# 1_SWAP_21DD__LV_DR_BRUSH_REV1_0_schdoc.net
KiCad netlist of a schematic drawn in Altium Designer
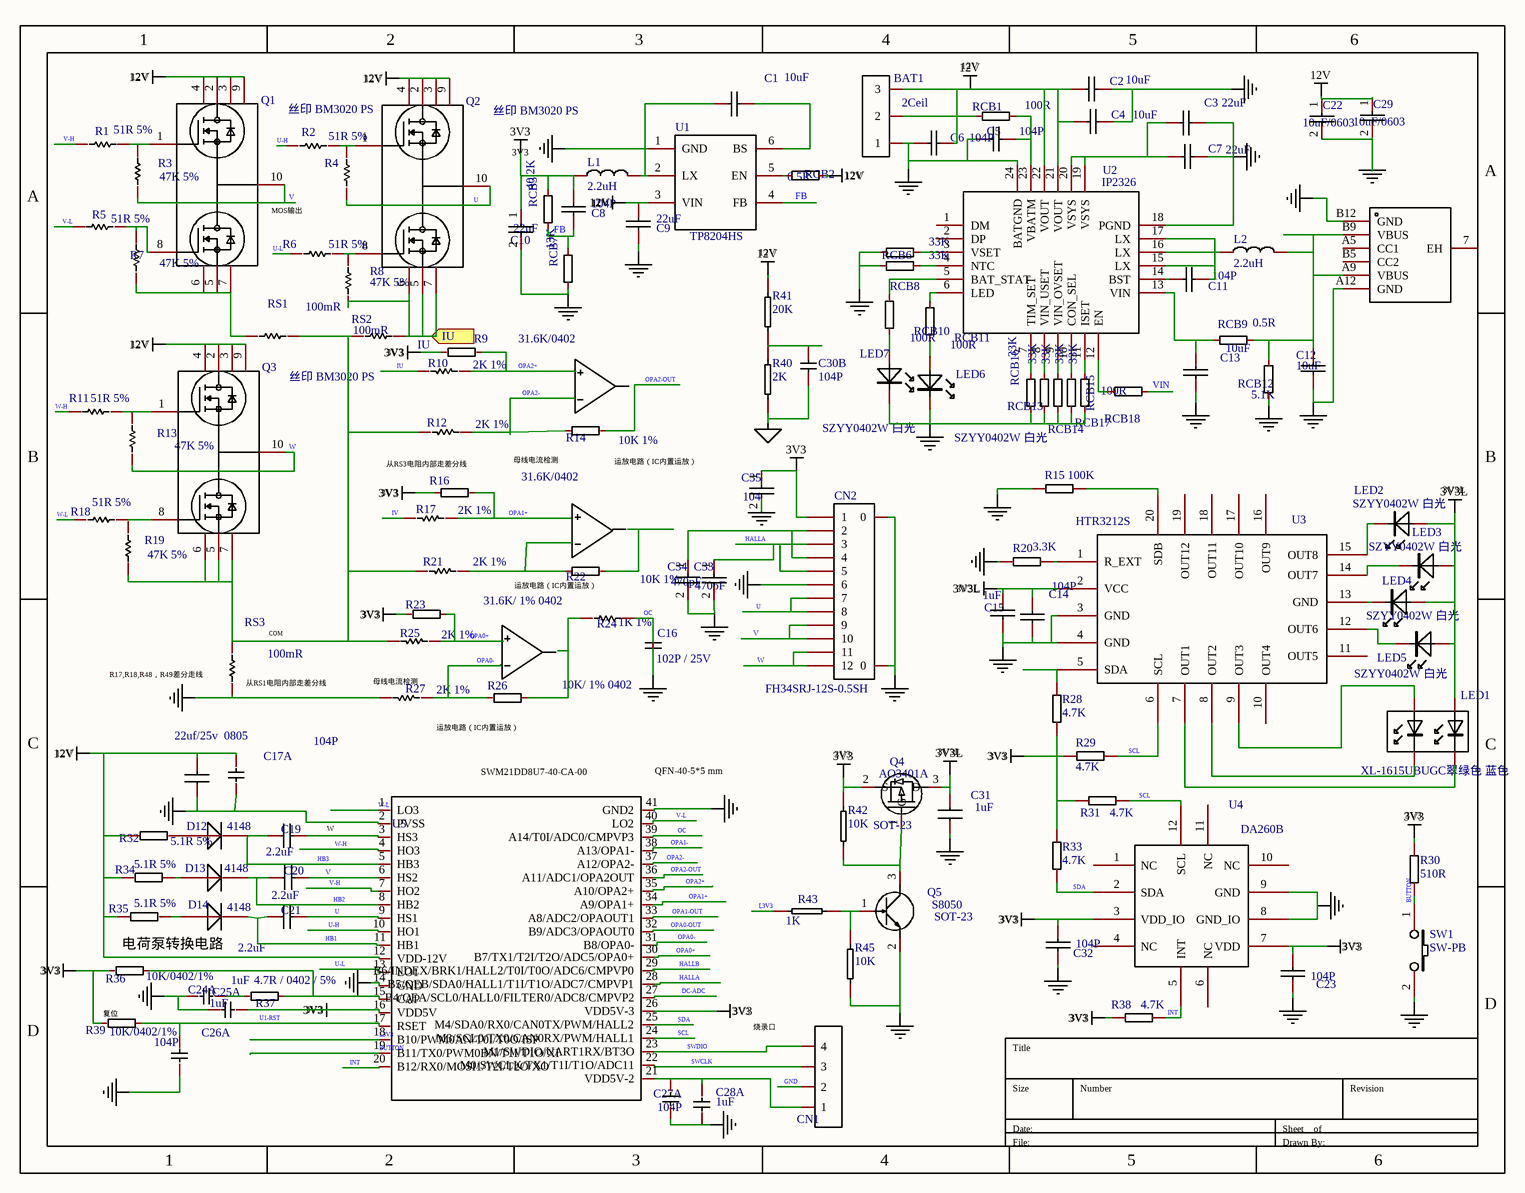
[diagram p0: 1_SWAP_21DD__LV_DR_BRUSH_REV1_0.schdoc.schdoc]

(export (version "E")
  (design (tool "Eeschema 10.0.6"))
  (components
    (comp (ref "BAT1")
      (value "BAT")
      (description "Connector")
      (libsource (lib "altium-import") (part "root_2_BAT_"))
    )
    (comp (ref "C1")
      (value "CC")
      (description "Capacitor")
      (libsource (lib "altium-import") (part "root_1_CC_"))
    )
    (comp (ref "C2")
      (value "CC")
      (description "Capacitor")
      (libsource (lib "altium-import") (part "root_3_CC_"))
    )
    (comp (ref "C3")
      (value "CC")
      (description "Capacitor")
      (libsource (lib "altium-import") (part "root_3_CC_"))
    )
    (comp (ref "C4")
      (value "CC")
      (description "Capacitor")
      (libsource (lib "altium-import") (part "root_3_CC_"))
    )
    (comp (ref "C5")
      (value "CC")
      (description "Capacitor")
      (libsource (lib "altium-import") (part "root_3_CC_"))
    )
    (comp (ref "C6")
      (value "CC")
      (description "Capacitor")
      (libsource (lib "altium-import") (part "root_3_CC_"))
    )
    (comp (ref "C7")
      (value "CC")
      (description "Capacitor")
      (libsource (lib "altium-import") (part "root_3_CC_"))
    )
    (comp (ref "C8")
      (value "CC")
      (description "Capacitor")
      (libsource (lib "altium-import") (part "root_0_CC_"))
    )
    (comp (ref "C9")
      (value "CC")
      (description "Capacitor")
      (libsource (lib "altium-import") (part "root_0_CC_"))
    )
    (comp (ref "C10") (value "CC") (description "Capacitor") (libsource (lib "") (part "root_0_CC__1")))
    (comp (ref "C11")
      (value "CC")
      (description "Capacitor")
      (libsource (lib "altium-import") (part "root_1_CC_"))
    )
    (comp (ref "C12")
      (value "CC")
      (description "Capacitor")
      (libsource (lib "altium-import") (part "root_0_CC_"))
    )
    (comp (ref "C13")
      (value "CC")
      (description "Capacitor")
      (libsource (lib "altium-import") (part "root_0_CC_"))
    )
    (comp (ref "C14")
      (value "CC")
      (description "Capacitor")
      (libsource (lib "altium-import") (part "root_0_CC_"))
    )
    (comp (ref "C15")
      (value "CC")
      (description "Capacitor")
      (libsource (lib "altium-import") (part "root_0_CC_"))
    )
    (comp (ref "C16")
      (value "C0603")
      (description "贴片瓷片电容")
      (fields (field (name "PUBLISHER") "Altium Limited"))
      (libsource (lib "altium-import") (part "root_2_C0603_"))
    )
    (comp (ref "C17") (value "CAP_S") (libsource (lib "altium-import") (part "root_2_CAP_S_")))
    (comp (ref "C18")
      (value "C0805")
      (description "SMT Resistor 5% UniOhm(厚声)")
      (fields
        (field (name "PUBLISHER") "Altium Limited")
        (field (name "SOURCE_PATH") "E:\\GTCS-A01-SWM-P9项目\\GTCS-A01-SWM-P9项目V1.2\\GTCS-A01-SWM-P9-V1.2.原理图\\99.DSN")
      )
      (libsource (lib "altium-import") (part "root_2_mirrored_C0805_"))
    )
    (comp (ref "C19")
      (value "C0805")
      (description "SMT Resistor 5% UniOhm(厚声)")
      (fields
        (field (name "PUBLISHER") "Altium Limited")
        (field (name "SOURCE_PATH") "E:\\GTCS-A01-SWM-P9项目\\GTCS-A01-SWM-P9项目V1.2\\GTCS-A01-SWM-P9-V1.2.原理图\\99.DSN")
      )
      (libsource (lib "altium-import") (part "root_1_C0805_"))
    )
    (comp (ref "C20")
      (value "C0805")
      (description "SMT Resistor 5% UniOhm(厚声)")
      (fields
        (field (name "PUBLISHER") "Altium Limited")
        (field (name "SOURCE_PATH") "E:\\GTCS-A01-SWM-P9项目\\GTCS-A01-SWM-P9项目V1.2\\GTCS-A01-SWM-P9-V1.2.原理图\\99.DSN")
      )
      (libsource (lib "altium-import") (part "root_1_C0805_"))
    )
    (comp (ref "C21")
      (value "C0805")
      (description "SMT Resistor 5% UniOhm(厚声)")
      (fields
        (field (name "PUBLISHER") "Altium Limited")
        (field (name "SOURCE_PATH") "E:\\GTCS-A01-SWM-P9项目\\GTCS-A01-SWM-P9项目V1.2\\GTCS-A01-SWM-P9-V1.2.原理图\\99.DSN")
      )
      (libsource (lib "altium-import") (part "root_1_C0805_"))
    )
    (comp (ref "C22")
      (value "CC")
      (description "Capacitor")
      (libsource (lib "altium-import") (part "root_0_mirrored_CC_"))
    )
    (comp (ref "C23")
      (value "CC")
      (description "Capacitor")
      (libsource (lib "altium-import") (part "root_0_CC_"))
    )
    (comp (ref "C24") (value "CAP_S") (libsource (lib "altium-import") (part "root_1_CAP_S_")))
    (comp (ref "C25") (value "CAP_S") (libsource (lib "altium-import") (part "root_3_CAP_S_")))
    (comp (ref "C26") (value "CAP_S") (libsource (lib "altium-import") (part "root_0_CAP_S_")))
    (comp (ref "C27") (value "CAP_S") (libsource (lib "altium-import") (part "root_2_CAP_S_")))
    (comp (ref "C28") (value "CAP_S") (libsource (lib "altium-import") (part "root_2_CAP_S_")))
    (comp (ref "C29")
      (value "CC")
      (description "Capacitor")
      (libsource (lib "altium-import") (part "root_0_mirrored_CC_"))
    )
    (comp (ref "C30") (value "CAP_S") (libsource (lib "altium-import") (part "root_2_CAP_S_")))
    (comp (ref "C31")
      (value "1uF")
      (fields (field (name "Comment") "CAPACITOR") (field (name "SOURCE_PATH") "F:\\T2700\\LIBRARY1.OLB"))
      (libsource (lib "altium-import") (part "root_0_CAPACITOR_"))
    )
    (comp (ref "C32")
      (value "CC")
      (description "Capacitor")
      (libsource (lib "altium-import") (part "root_0_CC_"))
    )
    (comp (ref "C33") (value "CC") (description "Capacitor") (libsource (lib "") (part "root_0_CC__1")))
    (comp (ref "C34") (value "CC") (description "Capacitor") (libsource (lib "") (part "root_0_CC__1")))
    (comp (ref "C35") (value "CC") (description "Capacitor") (libsource (lib "") (part "root_0_CC__1")))
    (comp (ref "CN1")
      (value "4P-2.54-8")
      (description "接插件  DS-5.1CN4  DS-2.54CWB-4")
      (libsource (lib "altium-import") (part "root_2_4P-2.54-8_"))
    )
    (comp (ref "CN2")
      (value "CON12")
      (description "Connector")
      (libsource (lib "altium-import") (part "root_0_CON12_"))
    )
    (comp (ref "D12")
      (value "DIODE")
      (description "Default Diode")
      (fields (field (name "PUBLISHER") "Altium Limited"))
      (libsource (lib "altium-import") (part "root_0_DIODE_"))
    )
    (comp (ref "D13")
      (value "DIODE")
      (description "Default Diode")
      (fields (field (name "PUBLISHER") "Altium Limited"))
      (libsource (lib "altium-import") (part "root_0_DIODE_"))
    )
    (comp (ref "D14")
      (value "DIODE")
      (description "Default Diode")
      (fields (field (name "PUBLISHER") "Altium Limited"))
      (libsource (lib "altium-import") (part "root_0_DIODE_"))
    )
    (comp (ref "L1")
      (value "L_-_5X4")
      (description "电感")
      (libsource (lib "altium-import") (part "root_0_L_-_5X4_"))
    )
    (comp (ref "L2")
      (value "L_-_5X4")
      (description "电感")
      (libsource (lib "altium-import") (part "root_0_L_-_5X4_"))
    )
    (comp (ref "LED1") (value "LED-1") (libsource (lib "altium-import") (part "root_3_LED-1_")))
    (comp (ref "LED2") (value "LED") (libsource (lib "altium-import") (part "root_2_LED_")))
    (comp (ref "LED3") (value "LED") (libsource (lib "altium-import") (part "root_2_LED_")))
    (comp (ref "LED4") (value "LED") (libsource (lib "altium-import") (part "root_2_LED_")))
    (comp (ref "LED5") (value "LED") (libsource (lib "altium-import") (part "root_2_LED_")))
    (comp (ref "LED6") (value "LED") (libsource (lib "altium-import") (part "root_3_LED_")))
    (comp (ref "LED7") (value "LED") (libsource (lib "altium-import") (part "root_3_LED_")))
    (comp (ref "Q1") (value "CJBM3020") (libsource (lib "altium-import") (part "root_0_CJBM3020_")))
    (comp (ref "Q2") (value "CJBM3020") (libsource (lib "altium-import") (part "root_0_CJBM3020_")))
    (comp (ref "Q3") (value "CJBM3020") (libsource (lib "altium-import") (part "root_0_CJBM3020_")))
    (comp (ref "Q4")
      (value "AO3401A")
      (fields
        (field (name "PCB_DECAL") "SOT-23")
        (field (name "Comment") "PMOS_3")
        (field (name "SOURCE_PATH") "F:\\T27XX\\MAIN BOARD\\T27XX_MAIN_V0D0_20211205.DSN")
      )
      (libsource (lib "altium-import") (part "root_1_mirrored_PMOS_3_"))
    )
    (comp (ref "Q5")
      (value "S8050")
      (fields
        (field (name "PCB_DECAL") "SOT-23")
        (field (name "Comment") "NPN")
        (field (name "SOURCE_PATH") "F:\\T2700\\LIBRARY1.OLB")
      )
      (libsource (lib "altium-import") (part "root_0_NPN_"))
    )
    (comp (ref "R1")
      (value "RES_SEMI")
      (description "Semiconductor Resistor")
      (fields (field (name "PUBLISHER") "Altium Limited"))
      (libsource (lib "altium-import") (part "root_0_RES_SEMI_"))
    )
    (comp (ref "R2")
      (value "RES_SEMI")
      (description "Semiconductor Resistor")
      (fields (field (name "PUBLISHER") "Altium Limited"))
      (libsource (lib "altium-import") (part "root_0_RES_SEMI_"))
    )
    (comp (ref "R3")
      (value "RES_SEMI")
      (description "Semiconductor Resistor")
      (fields (field (name "PUBLISHER") "Altium Limited"))
      (libsource (lib "altium-import") (part "root_1_RES_SEMI_"))
    )
    (comp (ref "R4")
      (value "RES_SEMI")
      (description "Semiconductor Resistor")
      (fields (field (name "PUBLISHER") "Altium Limited"))
      (libsource (lib "altium-import") (part "root_3_RES_SEMI_"))
    )
    (comp (ref "R5")
      (value "RES_SEMI")
      (description "Semiconductor Resistor")
      (fields (field (name "PUBLISHER") "Altium Limited"))
      (libsource (lib "altium-import") (part "root_0_RES_SEMI_"))
    )
    (comp (ref "R6")
      (value "RES_SEMI")
      (description "Semiconductor Resistor")
      (fields (field (name "PUBLISHER") "Altium Limited"))
      (libsource (lib "altium-import") (part "root_0_RES_SEMI_"))
    )
    (comp (ref "R7")
      (value "RES_SEMI")
      (description "Semiconductor Resistor")
      (fields (field (name "PUBLISHER") "Altium Limited"))
      (libsource (lib "altium-import") (part "root_1_RES_SEMI_"))
    )
    (comp (ref "R8")
      (value "RES_SEMI")
      (description "Semiconductor Resistor")
      (fields (field (name "PUBLISHER") "Altium Limited"))
      (libsource (lib "altium-import") (part "root_1_RES_SEMI_"))
    )
    (comp (ref "R9")
      (value "R0402")
      (description "贴片电阻")
      (fields (field (name "PUBLISHER") "Altium Limited"))
      (libsource (lib "altium-import") (part "root_0_mirrored_R0402_"))
    )
    (comp (ref "R10")
      (value "RES_SEMI")
      (description "Semiconductor Resistor")
      (fields (field (name "PUBLISHER") "Altium Limited"))
      (libsource (lib "altium-import") (part "root_2_mirrored_RES_SEMI_"))
    )
    (comp (ref "R11")
      (value "RES_SEMI")
      (description "Semiconductor Resistor")
      (fields (field (name "PUBLISHER") "Altium Limited"))
      (libsource (lib "altium-import") (part "root_0_RES_SEMI_"))
    )
    (comp (ref "R12")
      (value "RES_SEMI")
      (description "Semiconductor Resistor")
      (fields (field (name "PUBLISHER") "Altium Limited"))
      (libsource (lib "altium-import") (part "root_2_mirrored_RES_SEMI_"))
    )
    (comp (ref "R13")
      (value "RES_SEMI")
      (description "Semiconductor Resistor")
      (fields (field (name "PUBLISHER") "Altium Limited"))
      (libsource (lib "altium-import") (part "root_1_RES_SEMI_"))
    )
    (comp (ref "R14")
      (value "R0402")
      (description "贴片电阻")
      (fields (field (name "PUBLISHER") "Altium Limited"))
      (libsource (lib "altium-import") (part "root_0_mirrored_R0402_"))
    )
    (comp (ref "R15")
      (value "R")
      (description "Resistance")
      (libsource (lib "altium-import") (part "root_2_R_"))
    )
    (comp (ref "R16")
      (value "R0402")
      (description "贴片电阻")
      (fields (field (name "PUBLISHER") "Altium Limited"))
      (libsource (lib "altium-import") (part "root_0_mirrored_R0402_"))
    )
    (comp (ref "R17")
      (value "RES_SEMI")
      (description "Semiconductor Resistor")
      (fields (field (name "PUBLISHER") "Altium Limited"))
      (libsource (lib "altium-import") (part "root_2_mirrored_RES_SEMI_"))
    )
    (comp (ref "R18")
      (value "RES_SEMI")
      (description "Semiconductor Resistor")
      (fields (field (name "PUBLISHER") "Altium Limited"))
      (libsource (lib "altium-import") (part "root_0_RES_SEMI_"))
    )
    (comp (ref "R19")
      (value "RES_SEMI")
      (description "Semiconductor Resistor")
      (fields (field (name "PUBLISHER") "Altium Limited"))
      (libsource (lib "altium-import") (part "root_1_RES_SEMI_"))
    )
    (comp (ref "R20")
      (value "R")
      (description "Resistance")
      (libsource (lib "altium-import") (part "root_2_R_"))
    )
    (comp (ref "R21")
      (value "RES_SEMI")
      (description "Semiconductor Resistor")
      (fields (field (name "PUBLISHER") "Altium Limited"))
      (libsource (lib "altium-import") (part "root_2_mirrored_RES_SEMI_"))
    )
    (comp (ref "R22")
      (value "R0402")
      (description "贴片电阻")
      (fields (field (name "PUBLISHER") "Altium Limited"))
      (libsource (lib "altium-import") (part "root_0_mirrored_R0402_"))
    )
    (comp (ref "R23")
      (value "R0402")
      (description "贴片电阻")
      (fields (field (name "PUBLISHER") "Altium Limited"))
      (libsource (lib "altium-import") (part "root_0_mirrored_R0402_"))
    )
    (comp (ref "R24")
      (value "RES_SEMI")
      (description "Semiconductor Resistor")
      (fields (field (name "PUBLISHER") "Altium Limited"))
      (libsource (lib "altium-import") (part "root_0_RES_SEMI_"))
    )
    (comp (ref "R25")
      (value "RES_SEMI")
      (description "Semiconductor Resistor")
      (fields (field (name "PUBLISHER") "Altium Limited"))
      (libsource (lib "altium-import") (part "root_2_mirrored_RES_SEMI_"))
    )
    (comp (ref "R26")
      (value "R0402")
      (description "贴片电阻")
      (fields (field (name "PUBLISHER") "Altium Limited"))
      (libsource (lib "altium-import") (part "root_0_mirrored_R0402_"))
    )
    (comp (ref "R27")
      (value "RES_SEMI")
      (description "Semiconductor Resistor")
      (fields (field (name "PUBLISHER") "Altium Limited"))
      (libsource (lib "altium-import") (part "root_2_mirrored_RES_SEMI_"))
    )
    (comp (ref "R28")
      (value "R")
      (description "Resistance")
      (libsource (lib "altium-import") (part "root_3_R_"))
    )
    (comp (ref "R29")
      (value "R")
      (description "Resistance")
      (libsource (lib "altium-import") (part "root_0_R_"))
    )
    (comp (ref "R30")
      (value "R")
      (description "Resistance")
      (libsource (lib "altium-import") (part "root_3_R_"))
    )
    (comp (ref "R31")
      (value "R")
      (description "Resistance")
      (libsource (lib "altium-import") (part "root_0_R_"))
    )
    (comp (ref "R32") (value "RES_T") (libsource (lib "altium-import") (part "root_0_RES_T_")))
    (comp (ref "R33")
      (value "R")
      (description "Resistance")
      (libsource (lib "altium-import") (part "root_1_R_"))
    )
    (comp (ref "R34") (value "RES_T") (libsource (lib "altium-import") (part "root_0_RES_T_")))
    (comp (ref "R35") (value "RES_T") (libsource (lib "altium-import") (part "root_0_RES_T_")))
    (comp (ref "R36")
      (value "R0402")
      (description "贴片电阻")
      (fields (field (name "PUBLISHER") "Altium Limited"))
      (libsource (lib "altium-import") (part "root_0_R0402_"))
    )
    (comp (ref "R37")
      (value "R0402")
      (description "贴片电阻")
      (fields (field (name "PUBLISHER") "Altium Limited"))
      (libsource (lib "altium-import") (part "root_0_R0402_"))
    )
    (comp (ref "R38")
      (value "R")
      (description "Resistance")
      (libsource (lib "altium-import") (part "root_2_R_"))
    )
    (comp (ref "R39")
      (value "R0402")
      (description "贴片电阻")
      (fields (field (name "PUBLISHER") "Altium Limited"))
      (libsource (lib "altium-import") (part "root_0_R0402_"))
    )
    (comp (ref "R40") (value "RES1") (libsource (lib "altium-import") (part "root_1_RES1_")))
    (comp (ref "R41") (value "RES1") (libsource (lib "altium-import") (part "root_1_RES1_")))
    (comp (ref "R42") (value "RES1") (libsource (lib "altium-import") (part "root_1_RES1_")))
    (comp (ref "R43") (value "RES1") (libsource (lib "altium-import") (part "root_2_RES1_")))
    (comp (ref "R45") (value "RES1") (libsource (lib "altium-import") (part "root_3_RES1_")))
    (comp (ref "RCB1")
      (value "RR")
      (description "贴片 电阻器")
      (fields (field (name "PUBLISHER") "Altium Limited"))
      (libsource (lib "altium-import") (part "root_0_mirrored_RR_"))
    )
    (comp (ref "RCB2")
      (value "RR")
      (description "贴片 电阻器")
      (fields (field (name "PUBLISHER") "Altium Limited"))
      (libsource (lib "altium-import") (part "root_0_mirrored_RR_"))
    )
    (comp (ref "RCB3")
      (value "RR")
      (description "贴片 电阻器")
      (fields (field (name "PUBLISHER") "Altium Limited"))
      (libsource (lib "altium-import") (part "root_1_mirrored_RR_"))
    )
    (comp (ref "RCB6")
      (value "RR")
      (description "贴片 电阻器")
      (fields (field (name "PUBLISHER") "Altium Limited"))
      (libsource (lib "altium-import") (part "root_0_mirrored_RR_"))
    )
    (comp (ref "RCB7")
      (value "RR")
      (description "贴片 电阻器")
      (fields (field (name "PUBLISHER") "Altium Limited"))
      (libsource (lib "altium-import") (part "root_1_mirrored_RR_"))
    )
    (comp (ref "RCB8")
      (value "RR")
      (description "贴片 电阻器")
      (fields (field (name "PUBLISHER") "Altium Limited"))
      (libsource (lib "altium-import") (part "root_0_mirrored_RR_"))
    )
    (comp (ref "RCB9")
      (value "RR")
      (description "贴片 电阻器")
      (fields (field (name "PUBLISHER") "Altium Limited"))
      (libsource (lib "altium-import") (part "root_2_mirrored_RR_"))
    )
    (comp (ref "RCB10")
      (value "RR")
      (description "贴片 电阻器")
      (fields (field (name "PUBLISHER") "Altium Limited"))
      (libsource (lib "altium-import") (part "root_1_mirrored_RR_"))
    )
    (comp (ref "RCB11")
      (value "RR")
      (description "贴片 电阻器")
      (fields (field (name "PUBLISHER") "Altium Limited"))
      (libsource (lib "altium-import") (part "root_1_mirrored_RR_"))
    )
    (comp (ref "RCB12")
      (value "RR")
      (description "贴片 电阻器")
      (fields (field (name "PUBLISHER") "Altium Limited"))
      (libsource (lib "altium-import") (part "root_3_mirrored_RR_"))
    )
    (comp (ref "RCB13")
      (value "RR")
      (description "贴片 电阻器")
      (fields (field (name "PUBLISHER") "Altium Limited"))
      (libsource (lib "altium-import") (part "root_3_mirrored_RR_"))
    )
    (comp (ref "RCB14")
      (value "RR")
      (description "贴片 电阻器")
      (fields (field (name "PUBLISHER") "Altium Limited"))
      (libsource (lib "altium-import") (part "root_3_mirrored_RR_"))
    )
    (comp (ref "RCB15")
      (value "RR")
      (description "贴片 电阻器")
      (fields (field (name "PUBLISHER") "Altium Limited"))
      (libsource (lib "altium-import") (part "root_3_mirrored_RR_"))
    )
    (comp (ref "RCB16")
      (value "RR")
      (description "贴片 电阻器")
      (fields (field (name "PUBLISHER") "Altium Limited"))
      (libsource (lib "altium-import") (part "root_3_mirrored_RR_"))
    )
    (comp (ref "RCB17")
      (value "RR")
      (description "贴片 电阻器")
      (fields (field (name "PUBLISHER") "Altium Limited"))
      (libsource (lib "altium-import") (part "root_3_mirrored_RR_"))
    )
    (comp (ref "RCB18")
      (value "RR")
      (description "贴片 电阻器")
      (fields (field (name "PUBLISHER") "Altium Limited"))
      (libsource (lib "altium-import") (part "root_2_mirrored_RR_"))
    )
    (comp (ref "RS1")
      (value "RES_2512")
      (description "Semiconductor Resistor")
      (fields (field (name "PUBLISHER") "Altium Limited"))
      (libsource (lib "altium-import") (part "root_2_RES_2512_"))
    )
    (comp (ref "RS2")
      (value "RES_2512")
      (description "Semiconductor Resistor")
      (fields (field (name "PUBLISHER") "Altium Limited"))
      (libsource (lib "altium-import") (part "root_0_RES_2512_"))
    )
    (comp (ref "RS3")
      (value "RES_2512")
      (description "Semiconductor Resistor")
      (fields (field (name "PUBLISHER") "Altium Limited"))
      (libsource (lib "altium-import") (part "root_1_RES_2512_"))
    )
    (comp (ref "SW1") (value "SW-PB") (libsource (lib "altium-import") (part "root_3_SW-PB_")))
    (comp (ref "U1") (value "TP8204HS") (libsource (lib "altium-import") (part "root_0_TP8204HS_")))
    (comp (ref "U2") (value "IP2326") (libsource (lib "altium-import") (part "root_0_IP2326_")))
    (comp (ref "U3") (value "HTR3212S") (libsource (lib "altium-import") (part "root_0_HTR3212S_")))
    (comp (ref "U4") (value "DA260B") (libsource (lib "altium-import") (part "root_0_DA260B_")))
    (comp (ref "U5") (value "SWM21DD8U7") (libsource (lib "altium-import") (part "root_0_SWM21DD8U7_")))
    (comp (ref "USB1")
      (value "TYPE-C_6P")
      (fields
        (field (name "MANUFACTURER") "SHOU HAN(首韩)")
        (field (name "MANUFACTURER_PART") "TYPE-C 6P(073)")
      )
      (libsource (lib "altium-import") (part "root_0_TYPE-C_6P_"))
    )
  )
  (nets
    (net (code "1") (name "/BUTTON") (class "Default")
      (node (ref "R30") (pin "2") (pinfunction "2_2") (pintype "passive"))
      (node (ref "SW1") (pin "1") (pinfunction "1_1") (pintype "passive"))
      (node (ref "U5") (pin "19") (pinfunction "B11/TX0/PWM0BN/T1I/T1O/XI_19") (pintype "passive"))
    )
    (net (code "2") (name "/DC-ADC") (class "Default")
      (node (ref "U5") (pin "27") (pinfunction "B4/QEA/SCL0/HALL0/FILTER0/ADC8/CMPVP2_27") (pintype "passive"))
    )
    (net (code "3") (name "/FB") (class "Default")
      (node (ref "C8") (pin "2") (pinfunction "2_2") (pintype "passive"))
      (node (ref "RCB3") (pin "1") (pinfunction "1_1") (pintype "passive"))
      (node (ref "RCB7") (pin "2") (pinfunction "2_2") (pintype "passive"))
      (node (ref "U1") (pin "4") (pinfunction "FB_4") (pintype "passive"))
    )
    (net (code "4") (name "/HALLA") (class "Default")
      (node (ref "C33") (pin "1") (pinfunction "1_1") (pintype "passive"))
      (node (ref "CN2") (pin "3") (pinfunction "3_3") (pintype "passive"))
      (node (ref "CN2") (pin "5") (pinfunction "5_5") (pintype "passive"))
      (node (ref "U5") (pin "28") (pinfunction "B5/QEB/SDA0/HALL1/T1I/T1O/ADC7/CMPVP1_28") (pintype "passive"))
    )
    (net (code "5") (name "/HALLB") (class "Default")
      (node (ref "U5") (pin "29") (pinfunction "B6/INDEX/BRK1/HALL2/T0I/T0O/ADC6/CMPVP0_29") (pintype "passive"))
    )
    (net (code "6") (name "/HB1") (class "Default")
      (node (ref "C21") (pin "1") (pinfunction "1_1") (pintype "passive"))
      (node (ref "D14") (pin "2") (pinfunction "K_2") (pintype "passive"))
      (node (ref "U5") (pin "11") (pinfunction "HB1_11") (pintype "passive"))
    )
    (net (code "7") (name "/HB2") (class "Default")
      (node (ref "C20") (pin "1") (pinfunction "1_1") (pintype "passive"))
      (node (ref "D13") (pin "2") (pinfunction "K_2") (pintype "passive"))
      (node (ref "U5") (pin "8") (pinfunction "HB2_8") (pintype "passive"))
    )
    (net (code "8") (name "/HB3") (class "Default")
      (node (ref "C19") (pin "1") (pinfunction "1_1") (pintype "passive"))
      (node (ref "D12") (pin "2") (pinfunction "K_2") (pintype "passive"))
      (node (ref "U5") (pin "5") (pinfunction "HB3_5") (pintype "passive"))
    )
    (net (code "9") (name "/INT") (class "Default")
      (node (ref "R38") (pin "1") (pinfunction "1_1") (pintype "passive"))
      (node (ref "U4") (pin "5") (pinfunction "INT_5") (pintype "passive"))
      (node (ref "U5") (pin "20") (pinfunction "B12/RX0/MOSI1/T2I/T2O/XO_20") (pintype "passive"))
    )
    (net (code "10") (name "/IU") (class "Default")
      (node (ref "Q2") (pin "5") (pinfunction "S2_5") (pintype "passive"))
      (node (ref "Q2") (pin "6") (pinfunction "S2_6") (pintype "passive"))
      (node (ref "Q2") (pin "7") (pinfunction "S2_7") (pintype "passive"))
      (node (ref "R10") (pin "1") (pinfunction "1_1") (pintype "passive"))
      (node (ref "R8") (pin "1") (pinfunction "1_1") (pintype "passive"))
      (node (ref "RS2") (pin "2") (pinfunction "2_2") (pintype "passive"))
    )
    (net (code "11") (name "/IV") (class "Default")
      (node (ref "R17") (pin "1") (pinfunction "1_1") (pintype "passive"))
    )
    (net (code "12") (name "/L3V3") (class "Default")
      (node (ref "R43") (pin "2") (pinfunction "2_2") (pintype "passive"))
      (node (ref "U5") (pin "18") (pinfunction "B10/PWM0AN/T0I/T0O/ISP_18") (pintype "passive"))
    )
    (net (code "13") (name "/OC") (class "Default")
      (node (ref "C16") (pin "2") (pinfunction "2_2") (pintype "passive"))
      (node (ref "R24") (pin "2") (pinfunction "2_2") (pintype "passive"))
      (node (ref "U5") (pin "39") (pinfunction "A14/T0I/ADC0/CMPVP3_39") (pintype "passive"))
    )
    (net (code "14") (name "/OPA0+") (class "Default")
      (node (ref "R23") (pin "1") (pinfunction "1_1") (pintype "passive"))
      (node (ref "R25") (pin "2") (pinfunction "2_2") (pintype "passive"))
      (node (ref "U5") (pin "30") (pinfunction "B7/TX1/T2I/T2O/ADC5/OPA0+_30") (pintype "passive"))
    )
    (net (code "15") (name "/OPA0-") (class "Default")
      (node (ref "R26") (pin "2") (pinfunction "2_2") (pintype "passive"))
      (node (ref "R27") (pin "2") (pinfunction "2_2") (pintype "passive"))
      (node (ref "U5") (pin "31") (pinfunction "B8/OPA0-_31") (pintype "passive"))
    )
    (net (code "16") (name "/OPA0-OUT") (class "Default")
      (node (ref "U5") (pin "32") (pinfunction "B9/ADC3/OPAOUT0_32") (pintype "passive"))
    )
    (net (code "17") (name "/OPA1+") (class "Default")
      (node (ref "R16") (pin "1") (pinfunction "1_1") (pintype "passive"))
      (node (ref "R17") (pin "2") (pinfunction "2_2") (pintype "passive"))
      (node (ref "U5") (pin "34") (pinfunction "A9/OPA1+_34") (pintype "passive"))
    )
    (net (code "18") (name "/OPA1-") (class "Default")
      (node (ref "U5") (pin "38") (pinfunction "A13/OPA1-_38") (pintype "passive"))
    )
    (net (code "19") (name "/OPA1-OUT") (class "Default")
      (node (ref "U5") (pin "33") (pinfunction "A8/ADC2/OPAOUT1_33") (pintype "passive"))
    )
    (net (code "20") (name "/OPA2+") (class "Default")
      (node (ref "R10") (pin "2") (pinfunction "2_2") (pintype "passive"))
      (node (ref "R9") (pin "1") (pinfunction "1_1") (pintype "passive"))
      (node (ref "U5") (pin "35") (pinfunction "A10/OPA2+_35") (pintype "passive"))
    )
    (net (code "21") (name "/OPA2-") (class "Default")
      (node (ref "R12") (pin "2") (pinfunction "2_2") (pintype "passive"))
      (node (ref "R14") (pin "2") (pinfunction "2_2") (pintype "passive"))
      (node (ref "U5") (pin "37") (pinfunction "A12/OPA2-_37") (pintype "passive"))
    )
    (net (code "22") (name "/OPA2-OUT") (class "Default")
      (node (ref "R14") (pin "1") (pinfunction "1_1") (pintype "passive"))
      (node (ref "U5") (pin "36") (pinfunction "A11/ADC1/OPA2OUT_36") (pintype "passive"))
    )
    (net (code "23") (name "/SCL") (class "Default")
      (node (ref "R29") (pin "2") (pinfunction "2_2") (pintype "passive"))
      (node (ref "R31") (pin "2") (pinfunction "2_2") (pintype "passive"))
      (node (ref "U3") (pin "6") (pinfunction "SCL_6") (pintype "passive"))
      (node (ref "U4") (pin "12") (pinfunction "SCL_12") (pintype "passive"))
      (node (ref "U5") (pin "24") (pinfunction "M3/SCL0/TX0/CAN0RX/PWM/HALL1_24") (pintype "passive"))
    )
    (net (code "24") (name "/SDA") (class "Default")
      (node (ref "R33") (pin "1") (pinfunction "1_1") (pintype "passive"))
      (node (ref "U4") (pin "2") (pinfunction "SDA_2") (pintype "passive"))
      (node (ref "U5") (pin "25") (pinfunction "M4/SDA0/RX0/CAN0TX/PWM/HALL2_25") (pintype "passive"))
    )
    (net (code "25") (name "/SWCLK") (class "Default")
      (node (ref "CN1") (pin "3") (pinfunction "3_3") (pintype "passive"))
      (node (ref "U5") (pin "22") (pinfunction "M0/SWCLK/TX1/T1I/T1O/ADC11_22") (pintype "passive"))
    )
    (net (code "26") (name "/SWDIO") (class "Default")
      (node (ref "CN1") (pin "4") (pinfunction "4_4") (pintype "passive"))
      (node (ref "U5") (pin "23") (pinfunction "M1/SWDIO/UART1RX/BT3O_23") (pintype "passive"))
    )
    (net (code "27") (name "/U") (class "Default")
      (node (ref "C21") (pin "2") (pinfunction "2_2") (pintype "passive"))
      (node (ref "CN2") (pin "7") (pinfunction "7_7") (pintype "passive"))
      (node (ref "CN2") (pin "8") (pinfunction "8_8") (pintype "passive"))
      (node (ref "Q2") (pin "10") (pinfunction "S1/D2_10") (pintype "passive"))
      (node (ref "R4") (pin "2") (pinfunction "2_2") (pintype "passive"))
      (node (ref "U5") (pin "9") (pinfunction "HS1_9") (pintype "passive"))
    )
    (net (code "28") (name "/U-H") (class "Default")
      (node (ref "R2") (pin "1") (pinfunction "1_1") (pintype "passive"))
      (node (ref "U5") (pin "10") (pinfunction "HO1_10") (pintype "passive"))
    )
    (net (code "29") (name "/U-L") (class "Default")
      (node (ref "R6") (pin "1") (pinfunction "1_1") (pintype "passive"))
      (node (ref "U5") (pin "13") (pinfunction "LO1_13") (pintype "passive"))
    )
    (net (code "30") (name "/U1-RST") (class "Default")
      (node (ref "C26") (pin "1") (pinfunction "1_1") (pintype "passive"))
      (node (ref "R39") (pin "2") (pinfunction "2_2") (pintype "passive"))
      (node (ref "U5") (pin "17") (pinfunction "RSET_17") (pintype "passive"))
    )
    (net (code "31") (name "/V") (class "Default")
      (node (ref "C20") (pin "2") (pinfunction "2_2") (pintype "passive"))
      (node (ref "CN2") (pin "10") (pinfunction "10_10") (pintype "passive"))
      (node (ref "CN2") (pin "9") (pinfunction "9_9") (pintype "passive"))
      (node (ref "Q1") (pin "10") (pinfunction "S1/D2_10") (pintype "passive"))
      (node (ref "R3") (pin "1") (pinfunction "1_1") (pintype "passive"))
      (node (ref "U5") (pin "6") (pinfunction "HS2_6") (pintype "passive"))
    )
    (net (code "32") (name "/V-H") (class "Default")
      (node (ref "R1") (pin "1") (pinfunction "1_1") (pintype "passive"))
      (node (ref "U5") (pin "7") (pinfunction "HO2_7") (pintype "passive"))
    )
    (net (code "33") (name "/V-L") (class "Default")
      (node (ref "R5") (pin "1") (pinfunction "1_1") (pintype "passive"))
      (node (ref "U5") (pin "40") (pinfunction "LO2_40") (pintype "passive"))
    )
    (net (code "34") (name "/VIN") (class "Default")
      (node (ref "RCB18") (pin "2") (pinfunction "2_2") (pintype "passive"))
    )
    (net (code "35") (name "/W") (class "Default")
      (node (ref "CN2") (pin "11") (pinfunction "11_11") (pintype "passive"))
      (node (ref "CN2") (pin "12") (pinfunction "12_12") (pintype "passive"))
      (node (ref "Q3") (pin "10") (pinfunction "S1/D2_10") (pintype "passive"))
      (node (ref "R13") (pin "1") (pinfunction "1_1") (pintype "passive"))
    )
    (net (code "36") (name "/W-H") (class "Default")
      (node (ref "R11") (pin "1") (pinfunction "1_1") (pintype "passive"))
      (node (ref "U5") (pin "4") (pinfunction "HO3_4") (pintype "passive"))
    )
    (net (code "37") (name "/W-L") (class "Default")
      (node (ref "R18") (pin "1") (pinfunction "1_1") (pintype "passive"))
      (node (ref "U5") (pin "1") (pinfunction "LO3_1") (pintype "passive"))
    )
    (net (code "38") (name "3V3") (class "Default")
      (node (ref "C10") (pin "1") (pinfunction "1_1") (pintype "passive"))
      (node (ref "C23") (pin "1") (pinfunction "1_1") (pintype "passive"))
      (node (ref "C25") (pin "1") (pinfunction "1_1") (pintype "passive"))
      (node (ref "C32") (pin "1") (pinfunction "1_1") (pintype "passive"))
      (node (ref "C35") (pin "1") (pinfunction "1_1") (pintype "passive"))
      (node (ref "C8") (pin "1") (pinfunction "1_1") (pintype "passive"))
      (node (ref "CN2") (pin "1") (pinfunction "1_1") (pintype "passive"))
      (node (ref "L1") (pin "2") (pinfunction "2_2") (pintype "passive"))
      (node (ref "Q4") (pin "2") (pinfunction "S_2") (pintype "passive"))
      (node (ref "R16") (pin "2") (pinfunction "2_2") (pintype "passive"))
      (node (ref "R23") (pin "2") (pinfunction "2_2") (pintype "passive"))
      (node (ref "R28") (pin "2") (pinfunction "2_2") (pintype "passive"))
      (node (ref "R29") (pin "1") (pinfunction "1_1") (pintype "passive"))
      (node (ref "R30") (pin "1") (pinfunction "1_1") (pintype "passive"))
      (node (ref "R31") (pin "1") (pinfunction "1_1") (pintype "passive"))
      (node (ref "R33") (pin "2") (pinfunction "2_2") (pintype "passive"))
      (node (ref "R36") (pin "1") (pinfunction "1_1") (pintype "passive"))
      (node (ref "R38") (pin "2") (pinfunction "2_2") (pintype "passive"))
      (node (ref "R39") (pin "1") (pinfunction "1_1") (pintype "passive"))
      (node (ref "R42") (pin "2") (pinfunction "2_2") (pintype "passive"))
      (node (ref "R9") (pin "2") (pinfunction "2_2") (pintype "passive"))
      (node (ref "RCB3") (pin "2") (pinfunction "2_2") (pintype "passive"))
      (node (ref "U4") (pin "3") (pinfunction "VDD_IO_3") (pintype "passive"))
      (node (ref "U4") (pin "7") (pinfunction "VDD_7") (pintype "passive"))
      (node (ref "U5") (pin "16") (pinfunction "VDD5V_16") (pintype "passive"))
      (node (ref "U5") (pin "26") (pinfunction "VDD5V-3_26") (pintype "passive"))
    )
    (net (code "39") (name "3V3L") (class "Default")
      (node (ref "C14") (pin "1") (pinfunction "1_1") (pintype "passive"))
      (node (ref "C15") (pin "1") (pinfunction "1_1") (pintype "passive"))
      (node (ref "C31") (pin "1") (pinfunction "1_1") (pintype "passive"))
      (node (ref "LED1") (pin "3") (pintype "passive"))
      (node (ref "LED2") (pin "1") (pinfunction "1_1") (pintype "passive"))
      (node (ref "LED3") (pin "1") (pinfunction "1_1") (pintype "passive"))
      (node (ref "LED4") (pin "1") (pinfunction "1_1") (pintype "passive"))
      (node (ref "LED5") (pin "1") (pinfunction "1_1") (pintype "passive"))
      (node (ref "Q4") (pin "3") (pinfunction "D_3") (pintype "passive"))
      (node (ref "U3") (pin "2") (pinfunction "VCC_2") (pintype "passive"))
    )
    (net (code "40") (name "12V") (class "Default")
      (node (ref "BAT1") (pin "3") (pinfunction "3_3") (pintype "passive"))
      (node (ref "C17") (pin "2") (pinfunction "2_2") (pintype "passive"))
      (node (ref "C18") (pin "2") (pinfunction "2_2") (pintype "passive"))
      (node (ref "C2") (pin "2") (pinfunction "2_2") (pintype "passive"))
      (node (ref "C22") (pin "1") (pinfunction "1_1") (pintype "passive"))
      (node (ref "C29") (pin "1") (pinfunction "1_1") (pintype "passive"))
      (node (ref "C4") (pin "2") (pinfunction "2_2") (pintype "passive"))
      (node (ref "C6") (pin "1") (pinfunction "1_1") (pintype "passive"))
      (node (ref "C9") (pin "1") (pinfunction "1_1") (pintype "passive"))
      (node (ref "Q1") (pin "2") (pinfunction "D1_2") (pintype "passive"))
      (node (ref "Q1") (pin "3") (pinfunction "D1_3") (pintype "passive"))
      (node (ref "Q1") (pin "4") (pinfunction "D1_4") (pintype "passive"))
      (node (ref "Q1") (pin "9") (pinfunction "D1_9") (pintype "passive"))
      (node (ref "Q2") (pin "2") (pinfunction "D1_2") (pintype "passive"))
      (node (ref "Q2") (pin "3") (pinfunction "D1_3") (pintype "passive"))
      (node (ref "Q2") (pin "4") (pinfunction "D1_4") (pintype "passive"))
      (node (ref "Q2") (pin "9") (pinfunction "D1_9") (pintype "passive"))
      (node (ref "Q3") (pin "2") (pinfunction "D1_2") (pintype "passive"))
      (node (ref "Q3") (pin "3") (pinfunction "D1_3") (pintype "passive"))
      (node (ref "Q3") (pin "4") (pinfunction "D1_4") (pintype "passive"))
      (node (ref "Q3") (pin "9") (pinfunction "D1_9") (pintype "passive"))
      (node (ref "R32") (pin "1") (pinfunction "1_1") (pintype "passive"))
      (node (ref "R34") (pin "1") (pinfunction "1_1") (pintype "passive"))
      (node (ref "R35") (pin "1") (pinfunction "1_1") (pintype "passive"))
      (node (ref "R41") (pin "2") (pinfunction "2_2") (pintype "passive"))
      (node (ref "RCB2") (pin "1") (pinfunction "1_1") (pintype "passive"))
      (node (ref "U1") (pin "3") (pinfunction "VIN_3") (pintype "passive"))
      (node (ref "U2") (pin "21") (pinfunction "VOUT_21") (pintype "passive"))
      (node (ref "U2") (pin "22") (pinfunction "VOUT_22") (pintype "passive"))
      (node (ref "U5") (pin "12") (pinfunction "VDD-12V_12") (pintype "passive"))
    )
    (net (code "41") (name "GND") (class "Default")
      (node (ref "BAT1") (pin "1") (pinfunction "1_1") (pintype "passive"))
      (node (ref "C10") (pin "2") (pinfunction "2_2") (pintype "passive"))
      (node (ref "C12") (pin "2") (pinfunction "2_2") (pintype "passive"))
      (node (ref "C13") (pin "2") (pinfunction "2_2") (pintype "passive"))
      (node (ref "C14") (pin "2") (pinfunction "2_2") (pintype "passive"))
      (node (ref "C15") (pin "2") (pinfunction "2_2") (pintype "passive"))
      (node (ref "C16") (pin "1") (pinfunction "1_1") (pintype "passive"))
      (node (ref "C17") (pin "1") (pinfunction "1_1") (pintype "passive"))
      (node (ref "C18") (pin "1") (pinfunction "1_1") (pintype "passive"))
      (node (ref "C2") (pin "1") (pinfunction "1_1") (pintype "passive"))
      (node (ref "C22") (pin "2") (pinfunction "2_2") (pintype "passive"))
      (node (ref "C23") (pin "2") (pinfunction "2_2") (pintype "passive"))
      (node (ref "C24") (pin "1") (pinfunction "1_1") (pintype "passive"))
      (node (ref "C25") (pin "2") (pinfunction "2_2") (pintype "passive"))
      (node (ref "C26") (pin "2") (pinfunction "2_2") (pintype "passive"))
      (node (ref "C27") (pin "1") (pinfunction "1_1") (pintype "passive"))
      (node (ref "C28") (pin "1") (pinfunction "1_1") (pintype "passive"))
      (node (ref "C29") (pin "2") (pinfunction "2_2") (pintype "passive"))
      (node (ref "C3") (pin "1") (pinfunction "1_1") (pintype "passive"))
      (node (ref "C30") (pin "1") (pinfunction "1_1") (pintype "passive"))
      (node (ref "C31") (pin "2") (pinfunction "2_2") (pintype "passive"))
      (node (ref "C32") (pin "2") (pinfunction "2_2") (pintype "passive"))
      (node (ref "C33") (pin "2") (pinfunction "2_2") (pintype "passive"))
      (node (ref "C34") (pin "2") (pinfunction "2_2") (pintype "passive"))
      (node (ref "C35") (pin "2") (pinfunction "2_2") (pintype "passive"))
      (node (ref "C4") (pin "1") (pinfunction "1_1") (pintype "passive"))
      (node (ref "C5") (pin "2") (pinfunction "2_2") (pintype "passive"))
      (node (ref "C6") (pin "2") (pinfunction "2_2") (pintype "passive"))
      (node (ref "C7") (pin "1") (pinfunction "1_1") (pintype "passive"))
      (node (ref "C9") (pin "2") (pinfunction "2_2") (pintype "passive"))
      (node (ref "CN1") (pin "2") (pinfunction "2_2") (pintype "passive"))
      (node (ref "CN2") (pin "0") (pinfunction "0_0") (pintype "passive"))
      (node (ref "CN2") (pin "6") (pinfunction "6_6") (pintype "passive"))
      (node (ref "LED6") (pin "2") (pinfunction "2_2") (pintype "passive"))
      (node (ref "LED7") (pin "2") (pinfunction "2_2") (pintype "passive"))
      (node (ref "Q5") (pin "2") (pinfunction "E_2") (pintype "passive"))
      (node (ref "R15") (pin "2") (pinfunction "2_2") (pintype "passive"))
      (node (ref "R20") (pin "2") (pinfunction "2_2") (pintype "passive"))
      (node (ref "R27") (pin "1") (pinfunction "1_1") (pintype "passive"))
      (node (ref "R40") (pin "1") (pinfunction "1_1") (pintype "passive"))
      (node (ref "R45") (pin "2") (pinfunction "2_2") (pintype "passive"))
      (node (ref "RCB12") (pin "2") (pinfunction "2_2") (pintype "passive"))
      (node (ref "RCB13") (pin "2") (pinfunction "2_2") (pintype "passive"))
      (node (ref "RCB14") (pin "2") (pinfunction "2_2") (pintype "passive"))
      (node (ref "RCB15") (pin "2") (pinfunction "2_2") (pintype "passive"))
      (node (ref "RCB16") (pin "2") (pinfunction "2_2") (pintype "passive"))
      (node (ref "RCB17") (pin "2") (pinfunction "2_2") (pintype "passive"))
      (node (ref "RCB6") (pin "2") (pinfunction "2_2") (pintype "passive"))
      (node (ref "RCB7") (pin "1") (pinfunction "1_1") (pintype "passive"))
      (node (ref "RCB8") (pin "2") (pinfunction "2_2") (pintype "passive"))
      (node (ref "RS3") (pin "1") (pinfunction "1_1") (pintype "passive"))
      (node (ref "SW1") (pin "2") (pinfunction "2_2") (pintype "passive"))
      (node (ref "U1") (pin "1") (pinfunction "GND_1") (pintype "passive"))
      (node (ref "U2") (pin "18") (pinfunction "PGND_18") (pintype "passive"))
      (node (ref "U2") (pin "24") (pinfunction "BATGND_24") (pintype "passive"))
      (node (ref "U3") (pin "3") (pinfunction "GND_3") (pintype "passive"))
      (node (ref "U3") (pin "4") (pinfunction "GND_4") (pintype "passive"))
      (node (ref "U4") (pin "8") (pinfunction "GND_IO_8") (pintype "passive"))
      (node (ref "U4") (pin "9") (pinfunction "GND_9") (pintype "passive"))
      (node (ref "U5") (pin "14") (pinfunction "GND_14") (pintype "passive"))
      (node (ref "U5") (pin "2") (pinfunction "PVSS_2") (pintype "passive"))
      (node (ref "U5") (pin "41") (pinfunction "GND2_41") (pintype "passive"))
      (node (ref "USB1") (pin "A12") (pinfunction "GND_A12") (pintype "passive"))
      (node (ref "USB1") (pin "B12") (pinfunction "GND_B12") (pintype "passive"))
    )
    (net (code "42") (name "Net-(BAT1-Pad2)") (class "Default")
      (node (ref "BAT1") (pin "2") (pinfunction "2_2") (pintype "passive"))
      (node (ref "RCB1") (pin "2") (pinfunction "2_2") (pintype "passive"))
    )
    (net (code "43") (name "Net-(C3-Pad2)") (class "Default")
      (node (ref "C3") (pin "2") (pinfunction "2_2") (pintype "passive"))
      (node (ref "C7") (pin "2") (pinfunction "2_2") (pintype "passive"))
      (node (ref "U2") (pin "19") (pinfunction "VSYS_19") (pintype "passive"))
      (node (ref "U2") (pin "20") (pinfunction "VSYS_20") (pintype "passive"))
    )
    (net (code "44") (name "Net-(C11-Pad2)") (class "Default")
      (node (ref "C11") (pin "2") (pinfunction "2_2") (pintype "passive"))
      (node (ref "L2") (pin "2") (pinfunction "2_2") (pintype "passive"))
      (node (ref "U2") (pin "15") (pinfunction "LX_15") (pintype "passive"))
      (node (ref "U2") (pin "16") (pinfunction "LX_16") (pintype "passive"))
      (node (ref "U2") (pin "17") (pinfunction "LX_17") (pintype "passive"))
    )
    (net (code "45") (name "Net-(C12-Pad1)") (class "Default")
      (node (ref "C12") (pin "1") (pinfunction "1_1") (pintype "passive"))
      (node (ref "L2") (pin "1") (pinfunction "1_1") (pintype "passive"))
      (node (ref "RCB12") (pin "1") (pinfunction "1_1") (pintype "passive"))
      (node (ref "RCB9") (pin "2") (pinfunction "2_2") (pintype "passive"))
      (node (ref "USB1") (pin "A9") (pinfunction "VBUS_A9") (pintype "passive"))
      (node (ref "USB1") (pin "B9") (pinfunction "VBUS_B9") (pintype "passive"))
    )
    (net (code "46") (name "Net-(C24-Pad2)") (class "Default")
      (node (ref "C24") (pin "2") (pinfunction "2_2") (pintype "passive"))
      (node (ref "R37") (pin "1") (pinfunction "1_1") (pintype "passive"))
    )
    (net (code "47") (name "Net-(C30-Pad2)") (class "Default")
      (node (ref "C30") (pin "2") (pinfunction "2_2") (pintype "passive"))
      (node (ref "R40") (pin "2") (pinfunction "2_2") (pintype "passive"))
      (node (ref "R41") (pin "1") (pinfunction "1_1") (pintype "passive"))
    )
    (net (code "48") (name "Net-(C34-Pad1)") (class "Default")
      (node (ref "C34") (pin "1") (pinfunction "1_1") (pintype "passive"))
      (node (ref "CN2") (pin "2") (pinfunction "2_2") (pintype "passive"))
      (node (ref "CN2") (pin "4") (pinfunction "4_4") (pintype "passive"))
    )
    (net (code "49") (name "Net-(D12-A)") (class "Default")
      (node (ref "D12") (pin "1") (pinfunction "A_1") (pintype "passive"))
      (node (ref "R32") (pin "2") (pinfunction "2_2") (pintype "passive"))
    )
    (net (code "50") (name "Net-(D13-A)") (class "Default")
      (node (ref "D13") (pin "1") (pinfunction "A_1") (pintype "passive"))
      (node (ref "R34") (pin "2") (pinfunction "2_2") (pintype "passive"))
    )
    (net (code "51") (name "Net-(D14-A)") (class "Default")
      (node (ref "D14") (pin "1") (pinfunction "A_1") (pintype "passive"))
      (node (ref "R35") (pin "2") (pinfunction "2_2") (pintype "passive"))
    )
    (net (code "52") (name "Net-(LED4-Pad2)") (class "Default")
      (node (ref "LED4") (pin "2") (pinfunction "2_2") (pintype "passive"))
      (node (ref "U3") (pin "13") (pinfunction "GND_13") (pintype "passive"))
    )
    (net (code "53") (name "Net-(LED6-Pad1)") (class "Default")
      (node (ref "LED6") (pin "1") (pinfunction "1_1") (pintype "passive"))
      (node (ref "RCB11") (pin "1") (pinfunction "1_1") (pintype "passive"))
    )
    (net (code "54") (name "Net-(LED7-Pad1)") (class "Default")
      (node (ref "LED7") (pin "1") (pinfunction "1_1") (pintype "passive"))
      (node (ref "RCB10") (pin "1") (pinfunction "1_1") (pintype "passive"))
    )
    (net (code "55") (name "Net-(Q1-G1)") (class "Default")
      (node (ref "Q1") (pin "1") (pinfunction "G1_1") (pintype "passive"))
      (node (ref "R1") (pin "2") (pinfunction "2_2") (pintype "passive"))
      (node (ref "R3") (pin "2") (pinfunction "2_2") (pintype "passive"))
    )
    (net (code "56") (name "Net-(Q1-G2)") (class "Default")
      (node (ref "Q1") (pin "8") (pinfunction "G2_8") (pintype "passive"))
      (node (ref "R5") (pin "2") (pinfunction "2_2") (pintype "passive"))
      (node (ref "R7") (pin "2") (pinfunction "2_2") (pintype "passive"))
    )
    (net (code "57") (name "Net-(Q1-S2-Pad5)") (class "Default")
      (node (ref "Q1") (pin "5") (pinfunction "S2_5") (pintype "passive"))
      (node (ref "Q1") (pin "6") (pinfunction "S2_6") (pintype "passive"))
      (node (ref "Q1") (pin "7") (pinfunction "S2_7") (pintype "passive"))
      (node (ref "R7") (pin "1") (pinfunction "1_1") (pintype "passive"))
      (node (ref "RS1") (pin "2") (pinfunction "2_2") (pintype "passive"))
    )
    (net (code "58") (name "Net-(Q2-G1)") (class "Default")
      (node (ref "Q2") (pin "1") (pinfunction "G1_1") (pintype "passive"))
      (node (ref "R2") (pin "2") (pinfunction "2_2") (pintype "passive"))
      (node (ref "R4") (pin "1") (pinfunction "1_1") (pintype "passive"))
    )
    (net (code "59") (name "Net-(Q2-G2)") (class "Default")
      (node (ref "Q2") (pin "8") (pinfunction "G2_8") (pintype "passive"))
      (node (ref "R6") (pin "2") (pinfunction "2_2") (pintype "passive"))
      (node (ref "R8") (pin "2") (pinfunction "2_2") (pintype "passive"))
    )
    (net (code "60") (name "Net-(Q3-G1)") (class "Default")
      (node (ref "Q3") (pin "1") (pinfunction "G1_1") (pintype "passive"))
      (node (ref "R11") (pin "2") (pinfunction "2_2") (pintype "passive"))
      (node (ref "R13") (pin "2") (pinfunction "2_2") (pintype "passive"))
    )
    (net (code "61") (name "Net-(Q3-G2)") (class "Default")
      (node (ref "Q3") (pin "8") (pinfunction "G2_8") (pintype "passive"))
      (node (ref "R18") (pin "2") (pinfunction "2_2") (pintype "passive"))
    )
    (net (code "62") (name "Net-(Q3-S2-Pad5)") (class "Default")
      (node (ref "Q3") (pin "5") (pinfunction "S2_5") (pintype "passive"))
      (node (ref "Q3") (pin "6") (pinfunction "S2_6") (pintype "passive"))
      (node (ref "Q3") (pin "7") (pinfunction "S2_7") (pintype "passive"))
      (node (ref "R12") (pin "1") (pinfunction "1_1") (pintype "passive"))
      (node (ref "R19") (pin "1") (pinfunction "1_1") (pintype "passive"))
      (node (ref "R21") (pin "1") (pinfunction "1_1") (pintype "passive"))
      (node (ref "R25") (pin "1") (pinfunction "1_1") (pintype "passive"))
      (node (ref "RS1") (pin "1") (pinfunction "1_1") (pintype "passive"))
      (node (ref "RS2") (pin "1") (pinfunction "1_1") (pintype "passive"))
      (node (ref "RS3") (pin "2") (pinfunction "2_2") (pintype "passive"))
    )
    (net (code "63") (name "Net-(Q4-G)") (class "Default")
      (node (ref "Q4") (pin "1") (pinfunction "G_1") (pintype "passive"))
      (node (ref "Q5") (pin "3") (pinfunction "C_3") (pintype "passive"))
      (node (ref "R42") (pin "1") (pinfunction "1_1") (pintype "passive"))
    )
    (net (code "64") (name "Net-(Q5-B)") (class "Default")
      (node (ref "Q5") (pin "1") (pinfunction "B_1") (pintype "passive"))
      (node (ref "R43") (pin "1") (pinfunction "1_1") (pintype "passive"))
      (node (ref "R45") (pin "1") (pinfunction "1_1") (pintype "passive"))
    )
    (net (code "65") (name "Net-(R21-Pad2)") (class "Default")
      (node (ref "R21") (pin "2") (pinfunction "2_2") (pintype "passive"))
      (node (ref "R22") (pin "2") (pinfunction "2_2") (pintype "passive"))
    )
    (net (code "66") (name "Net-(R24-Pad1)") (class "Default")
      (node (ref "R24") (pin "1") (pinfunction "1_1") (pintype "passive"))
      (node (ref "R26") (pin "1") (pinfunction "1_1") (pintype "passive"))
    )
    (net (code "67") (name "Net-(U1-BS)") (class "Default")
      (node (ref "C1") (pin "2") (pinfunction "2_2") (pintype "passive"))
      (node (ref "U1") (pin "6") (pinfunction "BS_6") (pintype "passive"))
    )
    (net (code "68") (name "Net-(U1-EN)") (class "Default")
      (node (ref "RCB2") (pin "2") (pinfunction "2_2") (pintype "passive"))
      (node (ref "U1") (pin "5") (pinfunction "EN_5") (pintype "passive"))
    )
    (net (code "69") (name "Net-(U1-LX)") (class "Default")
      (node (ref "C1") (pin "1") (pinfunction "1_1") (pintype "passive"))
      (node (ref "L1") (pin "1") (pinfunction "1_1") (pintype "passive"))
      (node (ref "U1") (pin "2") (pinfunction "LX_2") (pintype "passive"))
    )
    (net (code "70") (name "Net-(U2-BAT_STAT)") (class "Default")
      (node (ref "RCB10") (pin "2") (pinfunction "2_2") (pintype "passive"))
      (node (ref "U2") (pin "5") (pinfunction "BAT_STAT_5") (pintype "passive"))
    )
    (net (code "71") (name "Net-(U2-BST)") (class "Default")
      (node (ref "C11") (pin "1") (pinfunction "1_1") (pintype "passive"))
      (node (ref "U2") (pin "14") (pinfunction "BST_14") (pintype "passive"))
    )
    (net (code "72") (name "Net-(U2-CON_SEL)") (class "Default")
      (node (ref "RCB17") (pin "1") (pinfunction "1_1") (pintype "passive"))
      (node (ref "U2") (pin "10") (pinfunction "CON_SEL_10") (pintype "passive"))
    )
    (net (code "73") (name "Net-(U2-EN)") (class "Default")
      (node (ref "RCB18") (pin "1") (pinfunction "1_1") (pintype "passive"))
      (node (ref "U2") (pin "12") (pinfunction "EN_12") (pintype "passive"))
    )
    (net (code "74") (name "Net-(U2-ISET)") (class "Default")
      (node (ref "RCB15") (pin "1") (pinfunction "1_1") (pintype "passive"))
      (node (ref "U2") (pin "11") (pinfunction "ISET_11") (pintype "passive"))
    )
    (net (code "75") (name "Net-(U2-LED)") (class "Default")
      (node (ref "RCB11") (pin "2") (pinfunction "2_2") (pintype "passive"))
      (node (ref "U2") (pin "6") (pinfunction "LED_6") (pintype "passive"))
    )
    (net (code "76") (name "Net-(U2-NTC)") (class "Default")
      (node (ref "RCB8") (pin "1") (pinfunction "1_1") (pintype "passive"))
      (node (ref "U2") (pin "4") (pinfunction "NTC_4") (pintype "passive"))
    )
    (net (code "77") (name "Net-(U2-TIM_SET)") (class "Default")
      (node (ref "RCB16") (pin "1") (pinfunction "1_1") (pintype "passive"))
      (node (ref "U2") (pin "7") (pinfunction "TIM_SET_7") (pintype "passive"))
    )
    (net (code "78") (name "Net-(U2-VBATM)") (class "Default")
      (node (ref "C5") (pin "1") (pinfunction "1_1") (pintype "passive"))
      (node (ref "RCB1") (pin "1") (pinfunction "1_1") (pintype "passive"))
      (node (ref "U2") (pin "23") (pinfunction "VBATM_23") (pintype "passive"))
    )
    (net (code "79") (name "Net-(U2-VIN)") (class "Default")
      (node (ref "C13") (pin "1") (pinfunction "1_1") (pintype "passive"))
      (node (ref "RCB9") (pin "1") (pinfunction "1_1") (pintype "passive"))
      (node (ref "U2") (pin "13") (pinfunction "VIN_13") (pintype "passive"))
    )
    (net (code "80") (name "Net-(U2-VIN_OVSET)") (class "Default")
      (node (ref "RCB14") (pin "1") (pinfunction "1_1") (pintype "passive"))
      (node (ref "U2") (pin "9") (pinfunction "VIN_OVSET_9") (pintype "passive"))
    )
    (net (code "81") (name "Net-(U2-VIN_USET)") (class "Default")
      (node (ref "RCB13") (pin "1") (pinfunction "1_1") (pintype "passive"))
      (node (ref "U2") (pin "8") (pinfunction "VIN_USET_8") (pintype "passive"))
    )
    (net (code "82") (name "Net-(U2-VSET)") (class "Default")
      (node (ref "RCB6") (pin "1") (pinfunction "1_1") (pintype "passive"))
      (node (ref "U2") (pin "3") (pinfunction "VSET_3") (pintype "passive"))
    )
    (net (code "83") (name "Net-(U3-OUT1)") (class "Default")
      (node (ref "LED1") (pin "2") (pintype "passive"))
      (node (ref "U3") (pin "7") (pinfunction "OUT1_7") (pintype "passive"))
    )
    (net (code "84") (name "Net-(U3-OUT2)") (class "Default")
      (node (ref "LED1") (pin "1") (pintype "passive"))
      (node (ref "U3") (pin "8") (pinfunction "OUT2_8") (pintype "passive"))
    )
    (net (code "85") (name "Net-(U3-OUT3)") (class "Default")
      (node (ref "LED1") (pin "4") (pintype "passive"))
      (node (ref "U3") (pin "9") (pinfunction "OUT3_9") (pintype "passive"))
    )
    (net (code "86") (name "Net-(U3-OUT6)") (class "Default")
      (node (ref "LED5") (pin "2") (pinfunction "2_2") (pintype "passive"))
      (node (ref "U3") (pin "12") (pinfunction "OUT6_12") (pintype "passive"))
    )
    (net (code "87") (name "Net-(U3-OUT7)") (class "Default")
      (node (ref "LED3") (pin "2") (pinfunction "2_2") (pintype "passive"))
      (node (ref "U3") (pin "14") (pinfunction "OUT7_14") (pintype "passive"))
    )
    (net (code "88") (name "Net-(U3-OUT8)") (class "Default")
      (node (ref "LED2") (pin "2") (pinfunction "2_2") (pintype "passive"))
      (node (ref "U3") (pin "15") (pinfunction "OUT8_15") (pintype "passive"))
    )
    (net (code "89") (name "Net-(U3-R_EXT)") (class "Default")
      (node (ref "R20") (pin "1") (pinfunction "1_1") (pintype "passive"))
      (node (ref "U3") (pin "1") (pinfunction "R_EXT_1") (pintype "passive"))
    )
    (net (code "90") (name "Net-(U3-SDA)") (class "Default")
      (node (ref "R28") (pin "1") (pinfunction "1_1") (pintype "passive"))
      (node (ref "U3") (pin "5") (pinfunction "SDA_5") (pintype "passive"))
    )
    (net (code "91") (name "Net-(U3-SDB)") (class "Default")
      (node (ref "R15") (pin "1") (pinfunction "1_1") (pintype "passive"))
      (node (ref "U3") (pin "20") (pinfunction "SDB_20") (pintype "passive"))
    )
    (net (code "92") (name "Net-(U5-CAP)") (class "Default")
      (node (ref "R36") (pin "2") (pinfunction "2_2") (pintype "passive"))
      (node (ref "R37") (pin "2") (pinfunction "2_2") (pintype "passive"))
      (node (ref "U5") (pin "15") (pinfunction "CAP_15") (pintype "passive"))
    )
    (net (code "93") (name "Net-(U5-HS3)") (class "Default")
      (node (ref "C19") (pin "2") (pinfunction "2_2") (pintype "passive"))
      (node (ref "U5") (pin "3") (pinfunction "HS3_3") (pintype "passive"))
    )
    (net (code "94") (name "Net-(U5-VDD5V-2)") (class "Default")
      (node (ref "C27") (pin "2") (pinfunction "2_2") (pintype "passive"))
      (node (ref "C28") (pin "2") (pinfunction "2_2") (pintype "passive"))
      (node (ref "CN1") (pin "1") (pinfunction "1_1") (pintype "passive"))
      (node (ref "U5") (pin "21") (pinfunction "VDD5V-2_21") (pintype "passive"))
    )
    (net (code "95") (name "unconnected-(R19-Pad2)") (class "Default")
      (node (ref "R19") (pin "2") (pinfunction "2_2") (pintype "passive"))
    )
    (net (code "96") (name "unconnected-(R22-Pad1)") (class "Default")
      (node (ref "R22") (pin "1") (pinfunction "1_1") (pintype "passive"))
    )
    (net (code "97") (name "unconnected-(U2-DM-Pad1)") (class "Default")
      (node (ref "U2") (pin "1") (pinfunction "DM_1") (pintype "passive"))
    )
    (net (code "98") (name "unconnected-(U2-DP-Pad2)") (class "Default")
      (node (ref "U2") (pin "2") (pinfunction "DP_2") (pintype "passive"))
    )
    (net (code "99") (name "unconnected-(U3-OUT4-Pad10)") (class "Default")
      (node (ref "U3") (pin "10") (pinfunction "OUT4_10") (pintype "passive"))
    )
    (net (code "100") (name "unconnected-(U3-OUT5-Pad11)") (class "Default")
      (node (ref "U3") (pin "11") (pinfunction "OUT5_11") (pintype "passive"))
    )
    (net (code "101") (name "unconnected-(U3-OUT9-Pad16)") (class "Default")
      (node (ref "U3") (pin "16") (pinfunction "OUT9_16") (pintype "passive"))
    )
    (net (code "102") (name "unconnected-(U3-OUT10-Pad17)") (class "Default")
      (node (ref "U3") (pin "17") (pinfunction "OUT10_17") (pintype "passive"))
    )
    (net (code "103") (name "unconnected-(U3-OUT11-Pad18)") (class "Default")
      (node (ref "U3") (pin "18") (pinfunction "OUT11_18") (pintype "passive"))
    )
    (net (code "104") (name "unconnected-(U3-OUT12-Pad19)") (class "Default")
      (node (ref "U3") (pin "19") (pinfunction "OUT12_19") (pintype "passive"))
    )
    (net (code "105") (name "unconnected-(U4-NC-Pad1)") (class "Default")
      (node (ref "U4") (pin "1") (pinfunction "NC_1") (pintype "passive"))
    )
    (net (code "106") (name "unconnected-(U4-NC-Pad4)") (class "Default")
      (node (ref "U4") (pin "4") (pinfunction "NC_4") (pintype "passive"))
    )
    (net (code "107") (name "unconnected-(U4-NC-Pad6)") (class "Default")
      (node (ref "U4") (pin "6") (pinfunction "NC_6") (pintype "passive"))
    )
    (net (code "108") (name "unconnected-(U4-NC-Pad10)") (class "Default")
      (node (ref "U4") (pin "10") (pinfunction "NC_10") (pintype "passive"))
    )
    (net (code "109") (name "unconnected-(U4-NC-Pad11)") (class "Default")
      (node (ref "U4") (pin "11") (pinfunction "NC_11") (pintype "passive"))
    )
    (net (code "110") (name "unconnected-(USB1-CC1-PadA5)") (class "Default")
      (node (ref "USB1") (pin "A5") (pinfunction "CC1_A5") (pintype "passive"))
    )
    (net (code "111") (name "unconnected-(USB1-CC2-PadB5)") (class "Default")
      (node (ref "USB1") (pin "B5") (pinfunction "CC2_B5") (pintype "passive"))
    )
    (net (code "112") (name "unconnected-(USB1-EH-Pad7)") (class "Default")
      (node (ref "USB1") (pin "7") (pinfunction "EH_7") (pintype "passive"))
    )
  )
)
